# HPMFeatherWing.net
KiCad netlist of a schematic drawn in EAGLE
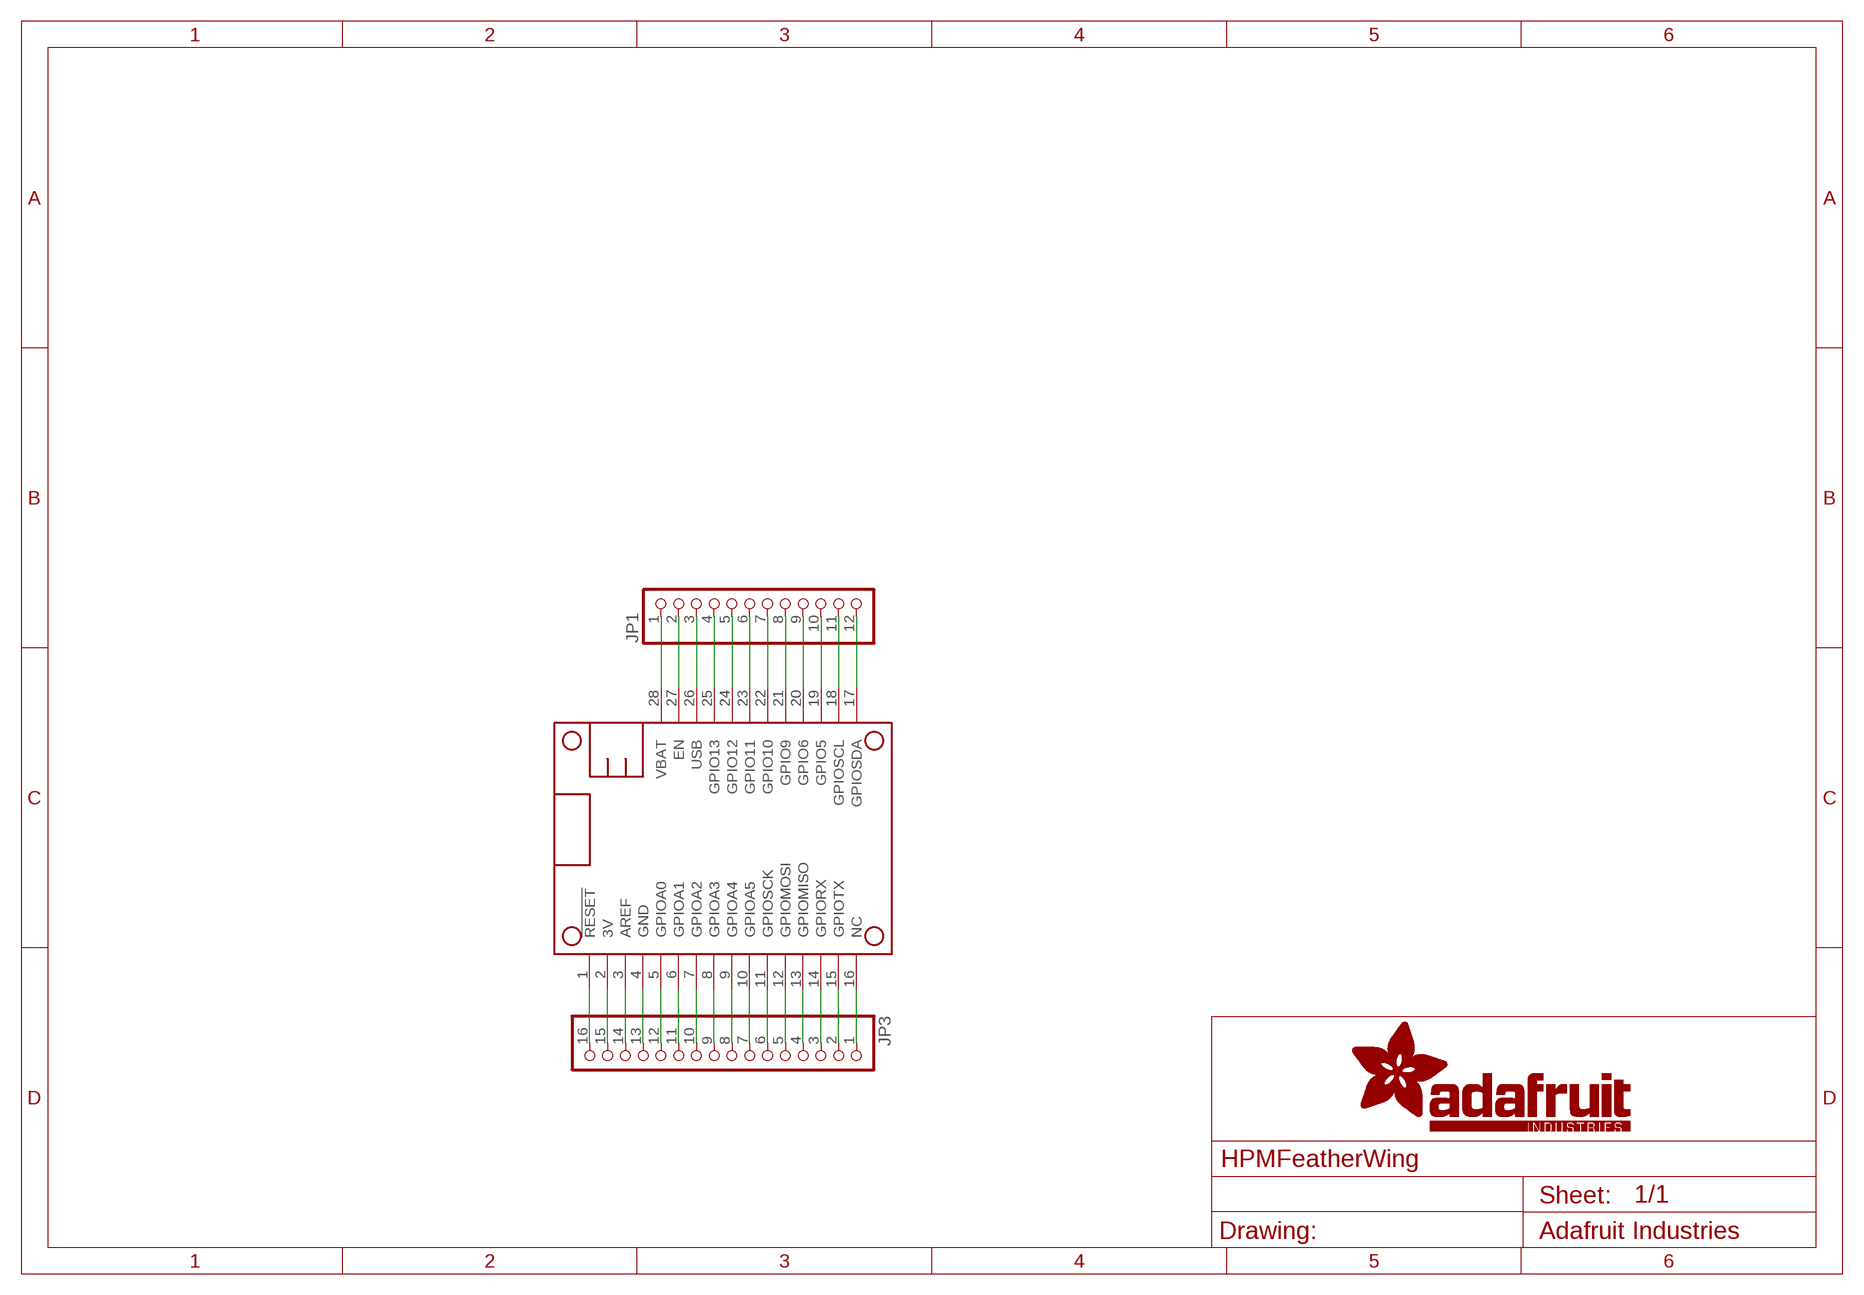
[diagram p0: schematic, sheet 1]

(export (version "E")
  (design (tool "Eeschema 10.0.6"))
  (components
    (comp (ref "JP1")
      (value "HEADER-1X1276MIL")
      (footprint "eagle-import:1X12_ROUND_76MIL")
      (libsource (lib "eagle-import") (part "HEADER-1X1276MIL"))
    )
    (comp (ref "JP3")
      (value "HEADER-1X16_76MIL")
      (footprint "eagle-import:1X16_ROUND_76MIL")
      (libsource (lib "eagle-import") (part "HEADER-1X16_76MIL"))
    )
    (comp (ref "MS1")
      (value "FEATHERWING")
      (footprint "eagle-import:FEATHERWING")
      (libsource (lib "eagle-import") (part "FEATHERWING"))
    )
  )
  (nets
    (net (code "1") (name "Net-(MS1-3V)") (class "Default")
      (node (ref "JP3") (pin "15") (pinfunction "15_15") (pintype "passive"))
      (node (ref "MS1") (pin "2") (pinfunction "3V_2") (pintype "power_in"))
    )
    (net (code "2") (name "Net-(MS1-AREF)") (class "Default")
      (node (ref "JP3") (pin "14") (pinfunction "14_14") (pintype "passive"))
      (node (ref "MS1") (pin "3") (pinfunction "AREF_3") (pintype "passive"))
    )
    (net (code "3") (name "Net-(MS1-EN)") (class "Default")
      (node (ref "JP1") (pin "2") (pinfunction "2_2") (pintype "passive"))
      (node (ref "MS1") (pin "27") (pinfunction "EN_27") (pintype "passive"))
    )
    (net (code "4") (name "Net-(MS1-GND)") (class "Default")
      (node (ref "JP3") (pin "13") (pinfunction "13_13") (pintype "passive"))
      (node (ref "MS1") (pin "4") (pinfunction "GND_4") (pintype "power_in"))
    )
    (net (code "5") (name "Net-(MS1-GPIO5)") (class "Default")
      (node (ref "JP1") (pin "10") (pinfunction "10_10") (pintype "passive"))
      (node (ref "MS1") (pin "19") (pinfunction "GPIO5_19") (pintype "bidirectional"))
    )
    (net (code "6") (name "Net-(MS1-GPIO6)") (class "Default")
      (node (ref "JP1") (pin "9") (pinfunction "9_9") (pintype "passive"))
      (node (ref "MS1") (pin "20") (pinfunction "GPIO6_20") (pintype "bidirectional"))
    )
    (net (code "7") (name "Net-(MS1-GPIO9)") (class "Default")
      (node (ref "JP1") (pin "8") (pinfunction "8_8") (pintype "passive"))
      (node (ref "MS1") (pin "21") (pinfunction "GPIO9_21") (pintype "bidirectional"))
    )
    (net (code "8") (name "Net-(MS1-GPIO10)") (class "Default")
      (node (ref "JP1") (pin "7") (pinfunction "7_7") (pintype "passive"))
      (node (ref "MS1") (pin "22") (pinfunction "GPIO10_22") (pintype "bidirectional"))
    )
    (net (code "9") (name "Net-(MS1-GPIO11)") (class "Default")
      (node (ref "JP1") (pin "6") (pinfunction "6_6") (pintype "passive"))
      (node (ref "MS1") (pin "23") (pinfunction "GPIO11_23") (pintype "bidirectional"))
    )
    (net (code "10") (name "Net-(MS1-GPIO12)") (class "Default")
      (node (ref "JP1") (pin "5") (pinfunction "5_5") (pintype "passive"))
      (node (ref "MS1") (pin "24") (pinfunction "GPIO12_24") (pintype "bidirectional"))
    )
    (net (code "11") (name "Net-(MS1-GPIO13)") (class "Default")
      (node (ref "JP1") (pin "4") (pinfunction "4_4") (pintype "passive"))
      (node (ref "MS1") (pin "25") (pinfunction "GPIO13_25") (pintype "bidirectional"))
    )
    (net (code "12") (name "Net-(MS1-GPIOA0)") (class "Default")
      (node (ref "JP3") (pin "12") (pinfunction "12_12") (pintype "passive"))
      (node (ref "MS1") (pin "5") (pinfunction "GPIOA0_5") (pintype "bidirectional"))
    )
    (net (code "13") (name "Net-(MS1-GPIOA1)") (class "Default")
      (node (ref "JP3") (pin "11") (pinfunction "11_11") (pintype "passive"))
      (node (ref "MS1") (pin "6") (pinfunction "GPIOA1_6") (pintype "bidirectional"))
    )
    (net (code "14") (name "Net-(MS1-GPIOA2)") (class "Default")
      (node (ref "JP3") (pin "10") (pinfunction "10_10") (pintype "passive"))
      (node (ref "MS1") (pin "7") (pinfunction "GPIOA2_7") (pintype "bidirectional"))
    )
    (net (code "15") (name "Net-(MS1-GPIOA3)") (class "Default")
      (node (ref "JP3") (pin "9") (pinfunction "9_9") (pintype "passive"))
      (node (ref "MS1") (pin "8") (pinfunction "GPIOA3_8") (pintype "bidirectional"))
    )
    (net (code "16") (name "Net-(MS1-GPIOA4)") (class "Default")
      (node (ref "JP3") (pin "8") (pinfunction "8_8") (pintype "passive"))
      (node (ref "MS1") (pin "9") (pinfunction "GPIOA4_9") (pintype "bidirectional"))
    )
    (net (code "17") (name "Net-(MS1-GPIOA5)") (class "Default")
      (node (ref "JP3") (pin "7") (pinfunction "7_7") (pintype "passive"))
      (node (ref "MS1") (pin "10") (pinfunction "GPIOA5_10") (pintype "bidirectional"))
    )
    (net (code "18") (name "Net-(MS1-GPIOMISO)") (class "Default")
      (node (ref "JP3") (pin "4") (pinfunction "4_4") (pintype "passive"))
      (node (ref "MS1") (pin "13") (pinfunction "GPIOMISO_13") (pintype "bidirectional"))
    )
    (net (code "19") (name "Net-(MS1-GPIOMOSI)") (class "Default")
      (node (ref "JP3") (pin "5") (pinfunction "5_5") (pintype "passive"))
      (node (ref "MS1") (pin "12") (pinfunction "GPIOMOSI_12") (pintype "bidirectional"))
    )
    (net (code "20") (name "Net-(MS1-GPIORX)") (class "Default")
      (node (ref "JP3") (pin "3") (pinfunction "3_3") (pintype "passive"))
      (node (ref "MS1") (pin "14") (pinfunction "GPIORX_14") (pintype "bidirectional"))
    )
    (net (code "21") (name "Net-(MS1-GPIOSCK)") (class "Default")
      (node (ref "JP3") (pin "6") (pinfunction "6_6") (pintype "passive"))
      (node (ref "MS1") (pin "11") (pinfunction "GPIOSCK_11") (pintype "bidirectional"))
    )
    (net (code "22") (name "Net-(MS1-GPIOSCL)") (class "Default")
      (node (ref "JP1") (pin "11") (pinfunction "11_11") (pintype "passive"))
      (node (ref "MS1") (pin "18") (pinfunction "GPIOSCL_18") (pintype "bidirectional"))
    )
    (net (code "23") (name "Net-(MS1-GPIOSDA)") (class "Default")
      (node (ref "JP1") (pin "12") (pinfunction "12_12") (pintype "passive"))
      (node (ref "MS1") (pin "17") (pinfunction "GPIOSDA_17") (pintype "bidirectional"))
    )
    (net (code "24") (name "Net-(MS1-GPIOTX)") (class "Default")
      (node (ref "JP3") (pin "2") (pinfunction "2_2") (pintype "passive"))
      (node (ref "MS1") (pin "15") (pinfunction "GPIOTX_15") (pintype "bidirectional"))
    )
    (net (code "25") (name "Net-(MS1-NC)") (class "Default")
      (node (ref "JP3") (pin "1") (pinfunction "1_1") (pintype "passive"))
      (node (ref "MS1") (pin "16") (pinfunction "NC_16") (pintype "passive"))
    )
    (net (code "26") (name "Net-(MS1-USB)") (class "Default")
      (node (ref "JP1") (pin "3") (pinfunction "3_3") (pintype "passive"))
      (node (ref "MS1") (pin "26") (pinfunction "USB_26") (pintype "power_in"))
    )
    (net (code "27") (name "Net-(MS1-VBAT)") (class "Default")
      (node (ref "JP1") (pin "1") (pinfunction "1_1") (pintype "passive"))
      (node (ref "MS1") (pin "28") (pinfunction "VBAT_28") (pintype "power_in"))
    )
    (net (code "28") (name "Net-(MS1-~{RESET})") (class "Default")
      (node (ref "JP3") (pin "16") (pinfunction "16_16") (pintype "passive"))
      (node (ref "MS1") (pin "1") (pinfunction "~{RESET}_1") (pintype "input"))
    )
  )
)
